# CPU_top.net
KiCad netlist of a schematic drawn in Altium Designer
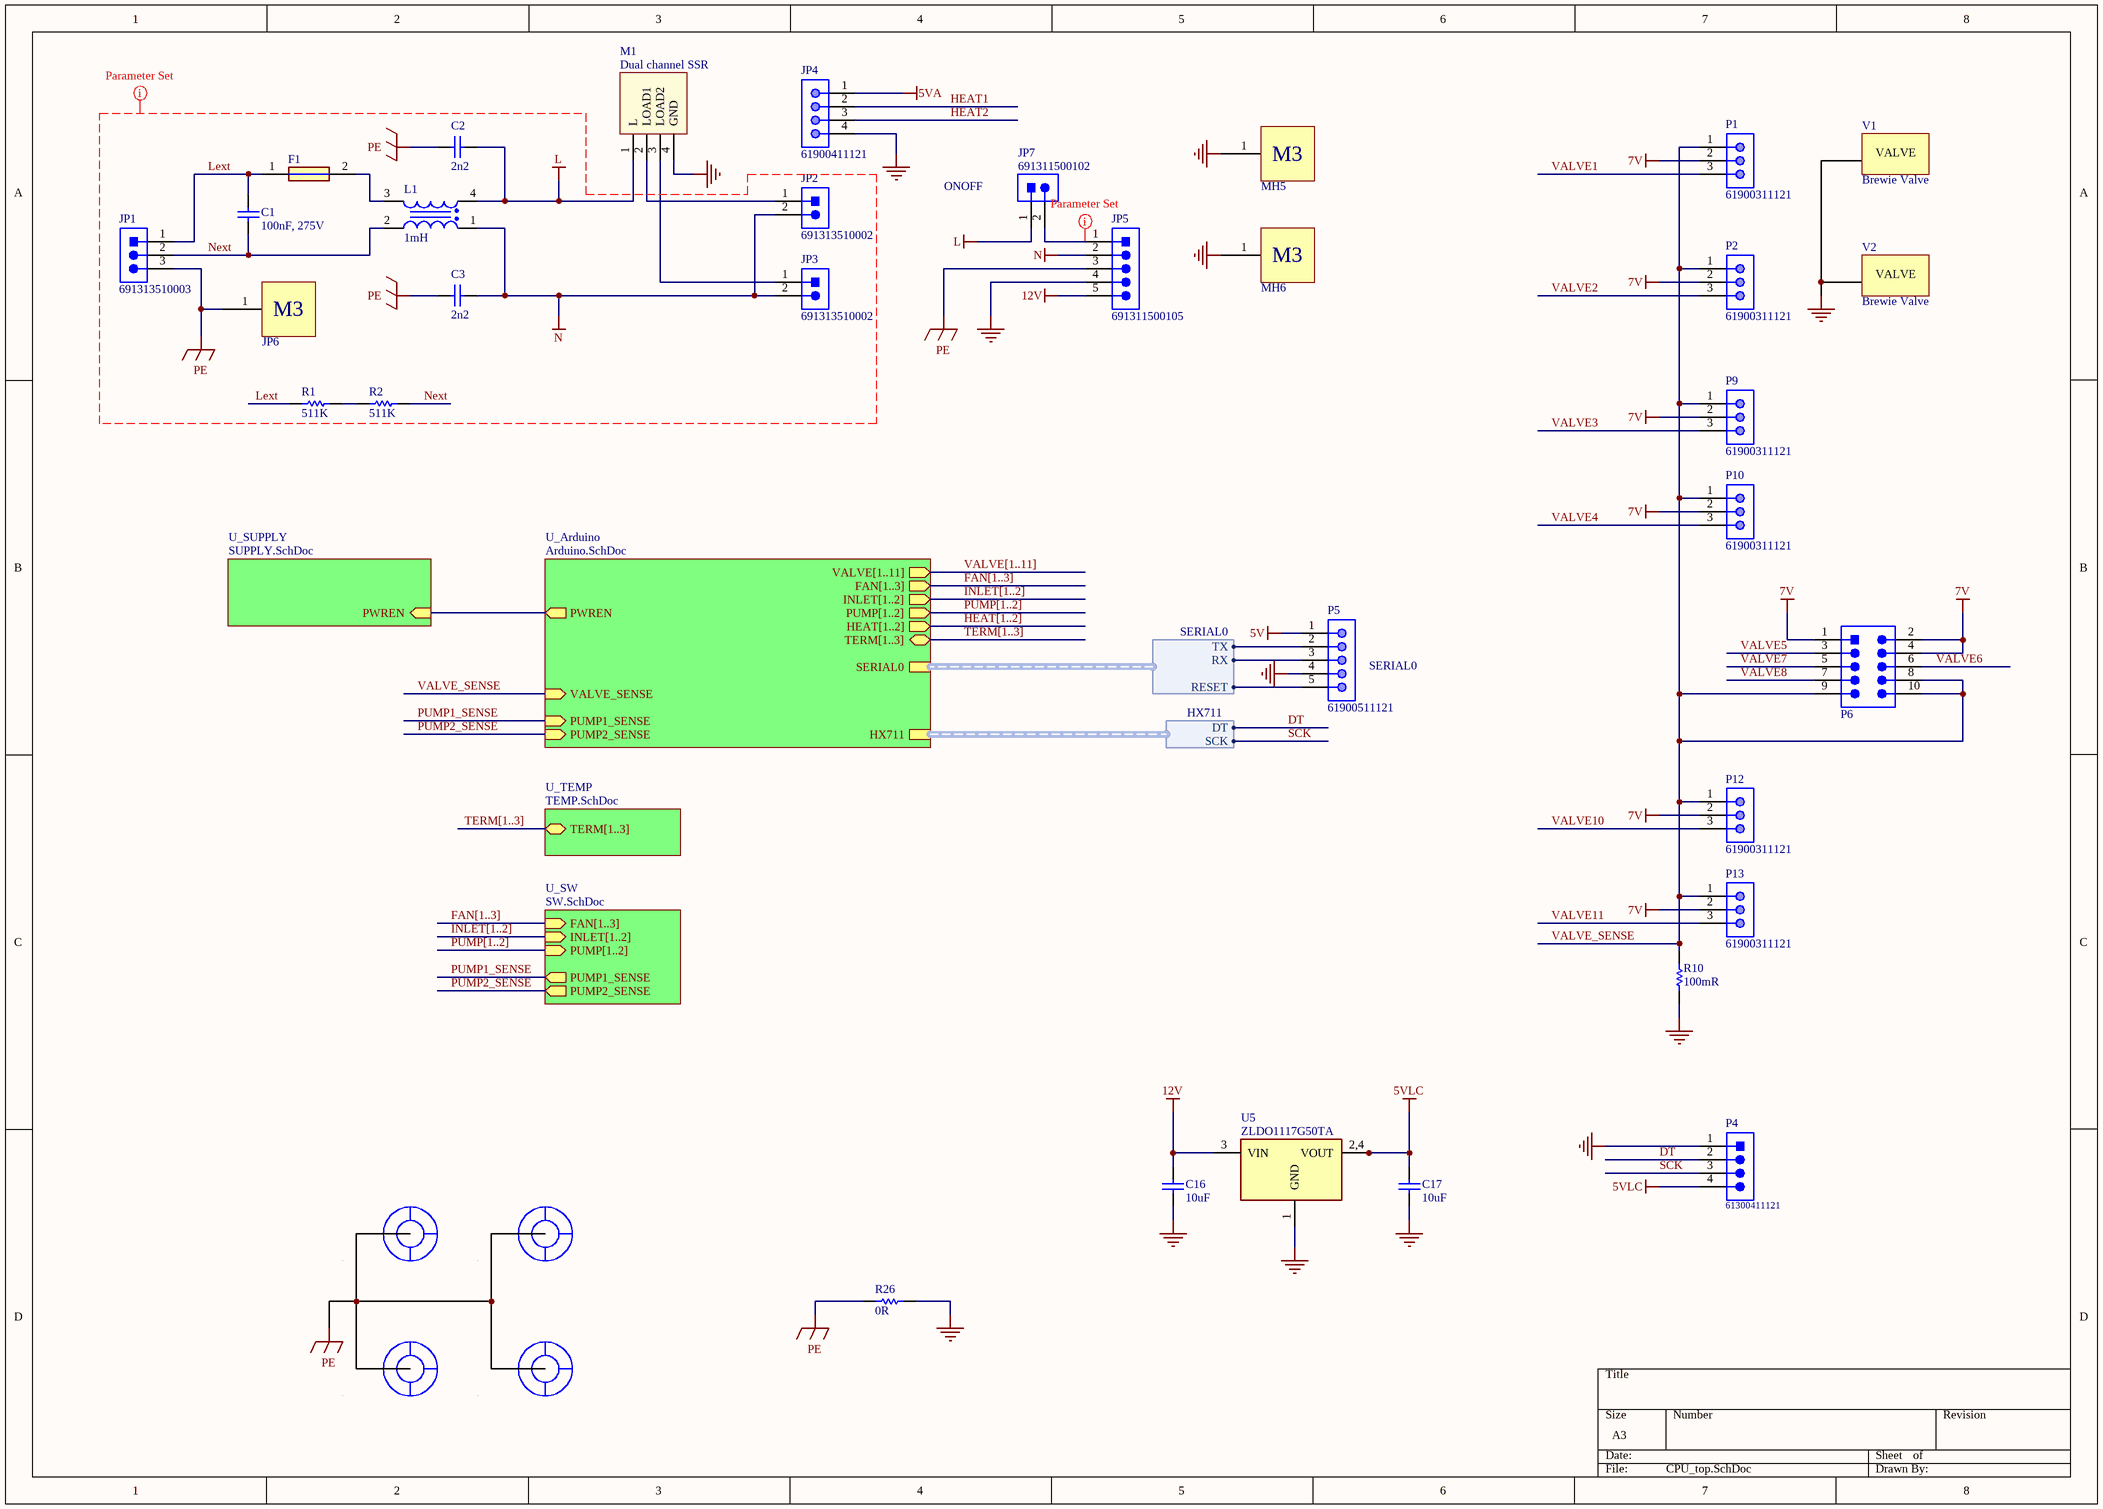
[diagram p0: CPU_top.SchDoc]

(export (version "E")
  (design (tool "Eeschema 10.0.6"))
  (components
    (comp (ref "C1")
      (value "100nF, 275V")
      (footprint "WCAP-FTX2_L13W7H13")
      (description "WCAP-FTX2 Film Capacitor, THT, L13W7H13, 100nF, 275V")
      (fields
        (field (name "MANUFACTURER") "Wurth Elektronik")
        (field (name "MANUFACTURER PART NUMBER") "890324023023")
      )
      (libsource (lib "Altium_WCAP-FTX2 (rev20a)") (part "890324023023"))
    )
    (comp (ref "C2")
      (value "2n2")
      (footprint "CAP CERDISC 9x5.5 P10 H13.0 (IPC RoHS)")
      (description "Cap X1Y1 2n2 400Vac 20% Y5V 4M E")
      (fields
        (field (name "PART NUMBER") "2235-0004")
        (field (name "Comment") "CAP")
        (field (name "CREATE") "Urband")
      )
      (libsource (lib "EEPAB-Altium-Lib") (part "CAP"))
    )
    (comp (ref "C3")
      (value "2n2")
      (footprint "CAP CERDISC 9x5.5 P10 H13.0 (IPC RoHS)")
      (description "Cap X1Y1 2n2 400Vac 20% Y5V 4M E")
      (fields
        (field (name "PART NUMBER") "2235-0004")
        (field (name "Comment") "CAP")
        (field (name "CREATE") "Urband")
      )
      (libsource (lib "EEPAB-Altium-Lib") (part "CAP"))
    )
    (comp (ref "C16")
      (value "10uF")
      (footprint "CAP_0805_H145 (_IPC_HD)")
      (description "CAP CER 10UF 16V X5R 0805")
      (fields (field (name "PART NUMBER") "0805YD106KAT2A") (field (name "Comment") "10uF 0805"))
      (libsource (lib "MUAB_Altium_Lib") (part "CAP"))
    )
    (comp (ref "C17")
      (value "10uF")
      (footprint "CAP_0805_H145 (_IPC_HD)")
      (description "CAP CER 10UF 16V X5R 0805")
      (fields (field (name "PART NUMBER") "0805YD106KAT2A") (field (name "Comment") "10uF 0805"))
      (libsource (lib "MUAB_Altium_Lib") (part "CAP"))
    )
    (comp (ref "F1")
      (value "SF-3812F1500T-2")
      (footprint "OpenBrewie:SF3812F1500T2")
      (description "Fuse")
      (fields (field (name "MOUSER PART NUMBER") "652-SF-3812F1500T-2"))
      (libsource (lib "OpenBrewie") (part "SF-3812F1500T-2"))
    )
    (comp (ref "JP1")
      (value "691313510003")
      (footprint "691313510003")
      (description "WR-TBL Serie 313 Close Horizontal PCB Header, Pluggable, THT, pitch 5.08mm, 3p")
      (fields (field (name "MANUFACTURER") "Wurth Elektronik"))
      (libsource (lib "Altium_WR-TBL (rev21a)") (part "691313510003"))
    )
    (comp (ref "JP2")
      (value "691313510002")
      (footprint "691313510002")
      (description "WR-TBL Serie 313 Close Horizontal PCB Header, Pluggable, THT, pitch 5.08mm, 2p")
      (fields (field (name "MANUFACTURER") "Wurth Elektronik"))
      (libsource (lib "Altium_WR-TBL (rev21a)") (part "691313510002"))
    )
    (comp (ref "JP3")
      (value "691313510002")
      (footprint "691313510002")
      (description "WR-TBL Serie 313 Close Horizontal PCB Header, Pluggable, THT, pitch 5.08mm, 2p")
      (fields (field (name "MANUFACTURER") "Wurth Elektronik"))
      (libsource (lib "Altium_WR-TBL (rev21a)") (part "691313510002"))
    )
    (comp (ref "JP4")
      (value "61900411121")
      (footprint "61900411121")
      (description "WR-WTB THT Male Vertical Locking Header, pitch 2.54mm, 4p")
      (fields (field (name "PUBLISHER") "Wurth Elektronik"))
      (libsource (lib "Altium_WR-WTB (rev20a)") (part "61900411121"))
    )
    (comp (ref "JP5")
      (value "691311500105")
      (footprint "691311500105")
      (description "WR-TBL Serie 311 Close Vertical PCB Header, Pluggable, THT, pitch 5.08mm, 5p")
      (fields (field (name "MANUFACTURER") "Wurth Elektronik"))
      (libsource (lib "Altium_WR-TBL (rev21a)") (part "691311500105"))
    )
    (comp (ref "JP6")
      (value "Adafruit Standoff 6mm")
      (footprint "7466003")
      (fields (field (name "MANUFACTURER") "Adafruit"))
      (libsource (lib "OpenBrewie") (part "CONNM3"))
    )
    (comp (ref "JP7")
      (value "691311500102")
      (footprint "691311500102")
      (description "WR-TBL Serie 311 Close Vertical PCB Header, Pluggable, THT, pitch 5.08mm, 2p")
      (fields (field (name "MANUFACTURER") "Wurth Elektronik"))
      (libsource (lib "Altium_WR-TBL (rev21a)") (part "691311500102"))
    )
    (comp (ref "L1")
      (value "1mH")
      (footprint "744834101")
      (description "WE-CMBH Common Mode Power Line Choke, Type L, 1mH")
      (fields
        (field (name "MANUFACTURER PART NUMBER") "744834101")
        (field (name "MANUFACTURER") "Wurth Elektronik")
      )
      (libsource (lib "WE-CMBH (rev20a)") (part "744834101"))
    )
    (comp (ref "M1") (value "Dual channel SSR") (footprint "SSR") (libsource (lib "OpenBrewie") (part "SSR")))
    (comp (ref "MH1")
      (value "Mounting hole")
      (footprint "MECH_MHOLE_3.5-GND-2")
      (libsource (lib "micun") (part "MECH_MHOLE_NET"))
    )
    (comp (ref "MH2")
      (value "Mounting hole")
      (footprint "MECH_MHOLE_3.5-GND-2")
      (libsource (lib "micun") (part "MECH_MHOLE_NET"))
    )
    (comp (ref "MH3")
      (value "Mounting hole")
      (footprint "MECH_MHOLE_3.5-GND-2")
      (libsource (lib "micun") (part "MECH_MHOLE_NET"))
    )
    (comp (ref "MH4")
      (value "Mounting hole")
      (footprint "MECH_MHOLE_3.5-GND-2")
      (libsource (lib "micun") (part "MECH_MHOLE_NET"))
    )
    (comp (ref "MH5")
      (value "Adafruit Standoff 6mm")
      (footprint "7466003")
      (fields (field (name "MANUFACTURER") "Adafruit"))
      (libsource (lib "OpenBrewie") (part "CONNM3"))
    )
    (comp (ref "MH6")
      (value "Adafruit Standoff 6mm")
      (footprint "7466003")
      (fields (field (name "MANUFACTURER") "Adafruit"))
      (libsource (lib "OpenBrewie") (part "CONNM3"))
    )
    (comp (ref "P1")
      (value "61900311121")
      (footprint "61900311121")
      (description "WR-WTB THT Male Vertical Locking Header, pitch 2.54mm, 3p")
      (fields (field (name "PUBLISHER") "Wurth Elektronik"))
      (libsource (lib "Altium_WR-WTB (rev20a)") (part "61900311121"))
    )
    (comp (ref "P2")
      (value "61900311121")
      (footprint "61900311121")
      (description "WR-WTB THT Male Vertical Locking Header, pitch 2.54mm, 3p")
      (fields (field (name "PUBLISHER") "Wurth Elektronik"))
      (libsource (lib "Altium_WR-WTB (rev20a)") (part "61900311121"))
    )
    (comp (ref "P4")
      (value "61300411121")
      (footprint "61300411121")
      (description "WR-PHD Pin Header, THT, pitch 2.54mm, Single Row, Vertical, 4p")
      (fields (field (name "MANUFACTURER") "Wurth Elektronik"))
      (libsource (lib "Altium_WR-PHD (rev22a)") (part "61300411121"))
    )
    (comp (ref "P5")
      (value "61900511121")
      (footprint "61900511121")
      (description "WR-WTB THT Male Vertical Locking Header, pitch 2.54mm, 5p")
      (fields (field (name "PUBLISHER") "Wurth Elektronik"))
      (libsource (lib "Altium_WR-WTB (rev20a)") (part "61900511121"))
    )
    (comp (ref "P6")
      (value "61201021621")
      (footprint "61201021621")
      (description "WR-BHD Box Header, Male, pitch 2.54mm, THT, Straight, 10p")
      (fields (field (name "MANUFACTURER") "Wurth Elektronik"))
      (libsource (lib "Altium_WR-BHD (rev22a)") (part "61201021621"))
    )
    (comp (ref "P9")
      (value "61900311121")
      (footprint "61900311121")
      (description "WR-WTB THT Male Vertical Locking Header, pitch 2.54mm, 3p")
      (fields (field (name "PUBLISHER") "Wurth Elektronik"))
      (libsource (lib "Altium_WR-WTB (rev20a)") (part "61900311121"))
    )
    (comp (ref "P10")
      (value "61900311121")
      (footprint "61900311121")
      (description "WR-WTB THT Male Vertical Locking Header, pitch 2.54mm, 3p")
      (fields (field (name "PUBLISHER") "Wurth Elektronik"))
      (libsource (lib "Altium_WR-WTB (rev20a)") (part "61900311121"))
    )
    (comp (ref "P12")
      (value "61900311121")
      (footprint "61900311121")
      (description "WR-WTB THT Male Vertical Locking Header, pitch 2.54mm, 3p")
      (fields (field (name "PUBLISHER") "Wurth Elektronik"))
      (libsource (lib "Altium_WR-WTB (rev20a)") (part "61900311121"))
    )
    (comp (ref "P13")
      (value "61900311121")
      (footprint "61900311121")
      (description "WR-WTB THT Male Vertical Locking Header, pitch 2.54mm, 3p")
      (fields (field (name "PUBLISHER") "Wurth Elektronik"))
      (libsource (lib "Altium_WR-WTB (rev20a)") (part "61900311121"))
    )
    (comp (ref "R1")
      (value "511K")
      (footprint "RES_1206_H060 (_IPC_MD)")
      (description "511K 1% 0,25W 200V 1206")
      (fields (field (name "PART NUMBER") "RES511K1%1206"))
      (libsource (lib "MUAB_Altium_Lib") (part "RES"))
    )
    (comp (ref "R2")
      (value "511K")
      (footprint "RES_1206_H060 (_IPC_MD)")
      (description "511K 1% 0,25W 200V 1206")
      (fields (field (name "PART NUMBER") "RES511K1%1206"))
      (libsource (lib "MUAB_Altium_Lib") (part "RES"))
    )
    (comp (ref "R10")
      (value "100mR")
      (footprint "RES_1206_H060 (_IPC_MD)")
      (description "100mR 1% 0,25W 200V 1206")
      (fields (field (name "PART NUMBER") "RES100mR1%1206"))
      (libsource (lib "MUAB_Altium_Lib") (part "RES"))
    )
    (comp (ref "R26")
      (value "0R")
      (footprint "RES_1206_H060 (_IPC_MD)")
      (description "JUMPER")
      (fields (field (name "PART NUMBER") "JUMPER1206"))
      (libsource (lib "MUAB_Altium_Lib") (part "RES"))
    )
    (comp (ref "U5")
      (value "ZLDO1117G50TA")
      (footprint "SOT230P700X180-4N")
      (description "IC REG LINEAR 3.3V 1A SOT223")
      (fields
        (field (name "MANUFACTURER_PART_NUMBER") "ZLDO1117G33TA")
        (field (name "MOUSER PART NUMBER") "522-ZLDO1117G33TA")
      )
      (libsource (lib "MUAB_Altium_Lib") (part "ZLDO1117G33TA"))
    )
    (comp (ref "V1")
      (value "Brewie Valve")
      (footprint "Valve2")
      (libsource (lib "OpenBrewie") (part "Valve"))
    )
    (comp (ref "V2")
      (value "Brewie Valve")
      (footprint "Valve2")
      (libsource (lib "OpenBrewie") (part "Valve"))
    )
  )
  (nets
    (net (code "14") (name "/DT") (class "Default")
      (node (ref "P4") (pin "2") (pinfunction "2_2") (pintype "passive"))
    )
    (net (code "16") (name "/HEAT1") (class "Default")
      (node (ref "JP4") (pin "2") (pinfunction "2_2") (pintype "passive"))
    )
    (net (code "17") (name "/HEAT2") (class "Default")
      (node (ref "JP4") (pin "3") (pinfunction "3_3") (pintype "passive"))
    )
    (net (code "20") (name "/Lext") (class "Default")
      (node (ref "C1") (pin "2") (pinfunction "2_2") (pintype "passive"))
      (node (ref "F1") (pin "1") (pinfunction "1_1") (pintype "passive"))
      (node (ref "JP1") (pin "1") (pinfunction "1_1") (pintype "passive"))
      (node (ref "R1") (pin "1") (pinfunction "1_1") (pintype "passive"))
    )
    (net (code "21") (name "/Next") (class "Default")
      (node (ref "C1") (pin "1") (pinfunction "1_1") (pintype "passive"))
      (node (ref "JP1") (pin "2") (pinfunction "2_2") (pintype "passive"))
      (node (ref "L1") (pin "2") (pinfunction "2_2") (pintype "passive"))
      (node (ref "R2") (pin "2") (pinfunction "2_2") (pintype "passive"))
    )
    (net (code "26") (name "/RESET") (class "Default")
      (node (ref "P5") (pin "5") (pinfunction "5_5") (pintype "passive"))
    )
    (net (code "27") (name "/RX") (class "Default")
      (node (ref "P5") (pin "3") (pinfunction "3_3") (pintype "passive"))
    )
    (net (code "28") (name "/SCK") (class "Default")
      (node (ref "P4") (pin "3") (pinfunction "3_3") (pintype "passive"))
    )
    (net (code "30") (name "/TX") (class "Default")
      (node (ref "P5") (pin "2") (pinfunction "2_2") (pintype "passive"))
    )
    (net (code "31") (name "/VALVE1") (class "Default")
      (node (ref "P1") (pin "3") (pinfunction "3_3") (pintype "passive"))
    )
    (net (code "32") (name "/VALVE2") (class "Default")
      (node (ref "P2") (pin "3") (pinfunction "3_3") (pintype "passive"))
    )
    (net (code "33") (name "/VALVE3") (class "Default")
      (node (ref "P9") (pin "3") (pinfunction "3_3") (pintype "passive"))
    )
    (net (code "34") (name "/VALVE4") (class "Default")
      (node (ref "P10") (pin "3") (pinfunction "3_3") (pintype "passive"))
    )
    (net (code "35") (name "/VALVE5") (class "Default")
      (node (ref "P6") (pin "3") (pinfunction "3_3") (pintype "passive"))
    )
    (net (code "36") (name "/VALVE6") (class "Default")
      (node (ref "P6") (pin "6") (pinfunction "6_6") (pintype "passive"))
    )
    (net (code "37") (name "/VALVE7") (class "Default")
      (node (ref "P6") (pin "5") (pinfunction "5_5") (pintype "passive"))
    )
    (net (code "38") (name "/VALVE8") (class "Default")
      (node (ref "P6") (pin "7") (pinfunction "7_7") (pintype "passive"))
    )
    (net (code "39") (name "/VALVE10") (class "Default")
      (node (ref "P12") (pin "3") (pinfunction "3_3") (pintype "passive"))
    )
    (net (code "40") (name "/VALVE11") (class "Default")
      (node (ref "P13") (pin "3") (pinfunction "3_3") (pintype "passive"))
    )
    (net (code "42") (name "/VALVE_SENSE") (class "Default")
      (node (ref "P1") (pin "1") (pinfunction "1_1") (pintype "passive"))
      (node (ref "P10") (pin "1") (pinfunction "1_1") (pintype "passive"))
      (node (ref "P12") (pin "1") (pinfunction "1_1") (pintype "passive"))
      (node (ref "P13") (pin "1") (pinfunction "1_1") (pintype "passive"))
      (node (ref "P2") (pin "1") (pinfunction "1_1") (pintype "passive"))
      (node (ref "P6") (pin "10") (pinfunction "10_10") (pintype "passive"))
      (node (ref "P6") (pin "8") (pinfunction "8_8") (pintype "passive"))
      (node (ref "P6") (pin "9") (pinfunction "9_9") (pintype "passive"))
      (node (ref "P9") (pin "1") (pinfunction "1_1") (pintype "passive"))
      (node (ref "R10") (pin "2") (pinfunction "2_2") (pintype "passive"))
    )
    (net (code "45") (name "5V") (class "Default")
      (node (ref "P5") (pin "1") (pinfunction "1_1") (pintype "passive"))
    )
    (net (code "46") (name "5VA") (class "Default")
      (node (ref "JP4") (pin "1") (pinfunction "1_1") (pintype "passive"))
    )
    (net (code "47") (name "5VLC") (class "Default")
      (node (ref "C17") (pin "2") (pinfunction "2_2") (pintype "passive"))
      (node (ref "P4") (pin "4") (pinfunction "4_4") (pintype "passive"))
      (node (ref "U5") (pin "2") (pinfunction "VOUT_1_2") (pintype "passive"))
      (node (ref "U5") (pin "4") (pinfunction "VOUT_4") (pintype "passive"))
    )
    (net (code "48") (name "7V") (class "Default")
      (node (ref "P1") (pin "2") (pinfunction "2_2") (pintype "passive"))
      (node (ref "P10") (pin "2") (pinfunction "2_2") (pintype "passive"))
      (node (ref "P12") (pin "2") (pinfunction "2_2") (pintype "passive"))
      (node (ref "P13") (pin "2") (pinfunction "2_2") (pintype "passive"))
      (node (ref "P2") (pin "2") (pinfunction "2_2") (pintype "passive"))
      (node (ref "P6") (pin "1") (pinfunction "1_1") (pintype "passive"))
      (node (ref "P6") (pin "2") (pinfunction "2_2") (pintype "passive"))
      (node (ref "P6") (pin "4") (pinfunction "4_4") (pintype "passive"))
      (node (ref "P9") (pin "2") (pinfunction "2_2") (pintype "passive"))
    )
    (net (code "49") (name "12V") (class "Default")
      (node (ref "C16") (pin "2") (pinfunction "2_2") (pintype "passive"))
      (node (ref "JP5") (pin "5") (pinfunction "5_5") (pintype "passive"))
      (node (ref "U5") (pin "3") (pinfunction "VIN_3") (pintype "passive"))
    )
    (net (code "50") (name "GND") (class "Default")
      (node (ref "C16") (pin "1") (pinfunction "1_1") (pintype "passive"))
      (node (ref "C17") (pin "1") (pinfunction "1_1") (pintype "passive"))
      (node (ref "JP4") (pin "4") (pinfunction "4_4") (pintype "passive"))
      (node (ref "JP5") (pin "4") (pinfunction "4_4") (pintype "passive"))
      (node (ref "M1") (pin "4") (pinfunction "GND_4") (pintype "passive"))
      (node (ref "MH5") (pin "1") (pinfunction "1_1") (pintype "passive"))
      (node (ref "MH6") (pin "1") (pinfunction "1_1") (pintype "passive"))
      (node (ref "P4") (pin "1") (pinfunction "1_1") (pintype "passive"))
      (node (ref "P5") (pin "4") (pinfunction "4_4") (pintype "passive"))
      (node (ref "R10") (pin "1") (pinfunction "1_1") (pintype "passive"))
      (node (ref "R26") (pin "2") (pinfunction "2_2") (pintype "passive"))
      (node (ref "U5") (pin "1") (pinfunction "GND_1") (pintype "passive"))
      (node (ref "V1") (pin "1") (pinfunction "CONN_1") (pintype "power_in"))
      (node (ref "V2") (pin "1") (pinfunction "CONN_1") (pintype "power_in"))
    )
    (net (code "51") (name "L") (class "Default")
      (node (ref "C2") (pin "2") (pinfunction "2_2") (pintype "passive"))
      (node (ref "JP7") (pin "1") (pinfunction "1_1") (pintype "passive"))
      (node (ref "L1") (pin "4") (pinfunction "4_4") (pintype "passive"))
      (node (ref "M1") (pin "1") (pinfunction "L_1") (pintype "passive"))
    )
    (net (code "52") (name "N") (class "Default")
      (node (ref "C3") (pin "2") (pinfunction "2_2") (pintype "passive"))
      (node (ref "JP2") (pin "2") (pinfunction "2_2") (pintype "passive"))
      (node (ref "JP3") (pin "2") (pinfunction "2_2") (pintype "passive"))
      (node (ref "JP5") (pin "2") (pinfunction "2_2") (pintype "passive"))
      (node (ref "L1") (pin "1") (pinfunction "1_1") (pintype "passive"))
    )
    (net (code "53") (name "Net-(F1-Pad2)") (class "Default")
      (node (ref "F1") (pin "2") (pinfunction "2_2") (pintype "passive"))
      (node (ref "L1") (pin "3") (pinfunction "3_3") (pintype "passive"))
    )
    (net (code "54") (name "Net-(JP5-Pad1)") (class "Default")
      (node (ref "JP5") (pin "1") (pinfunction "1_1") (pintype "passive"))
      (node (ref "JP7") (pin "2") (pinfunction "2_2") (pintype "passive"))
    )
    (net (code "55") (name "Net-(M1-LOAD1)") (class "Default")
      (node (ref "JP2") (pin "1") (pinfunction "1_1") (pintype "passive"))
      (node (ref "M1") (pin "2") (pinfunction "LOAD1_2") (pintype "passive"))
    )
    (net (code "56") (name "Net-(M1-LOAD2)") (class "Default")
      (node (ref "JP3") (pin "1") (pinfunction "1_1") (pintype "passive"))
      (node (ref "M1") (pin "3") (pinfunction "LOAD2_3") (pintype "passive"))
    )
    (net (code "57") (name "Net-(R1-Pad2)") (class "Default")
      (node (ref "R1") (pin "2") (pinfunction "2_2") (pintype "passive"))
      (node (ref "R2") (pin "1") (pinfunction "1_1") (pintype "passive"))
    )
    (net (code "58") (name "PE") (class "Default")
      (node (ref "C2") (pin "1") (pinfunction "1_1") (pintype "passive"))
      (node (ref "C3") (pin "1") (pinfunction "1_1") (pintype "passive"))
      (node (ref "JP1") (pin "3") (pinfunction "3_3") (pintype "passive"))
      (node (ref "JP5") (pin "3") (pinfunction "3_3") (pintype "passive"))
      (node (ref "JP6") (pin "1") (pinfunction "1_1") (pintype "passive"))
      (node (ref "MH1") (pin "1") (pinfunction "NET_1") (pintype "power_in"))
      (node (ref "MH2") (pin "1") (pinfunction "NET_1") (pintype "power_in"))
      (node (ref "MH3") (pin "1") (pinfunction "NET_1") (pintype "power_in"))
      (node (ref "MH4") (pin "1") (pinfunction "NET_1") (pintype "power_in"))
      (node (ref "R26") (pin "1") (pinfunction "1_1") (pintype "passive"))
    )
  )
)
